# TSOC_CYBLE_R1_0.net
KiCad netlist of a schematic drawn in EAGLE
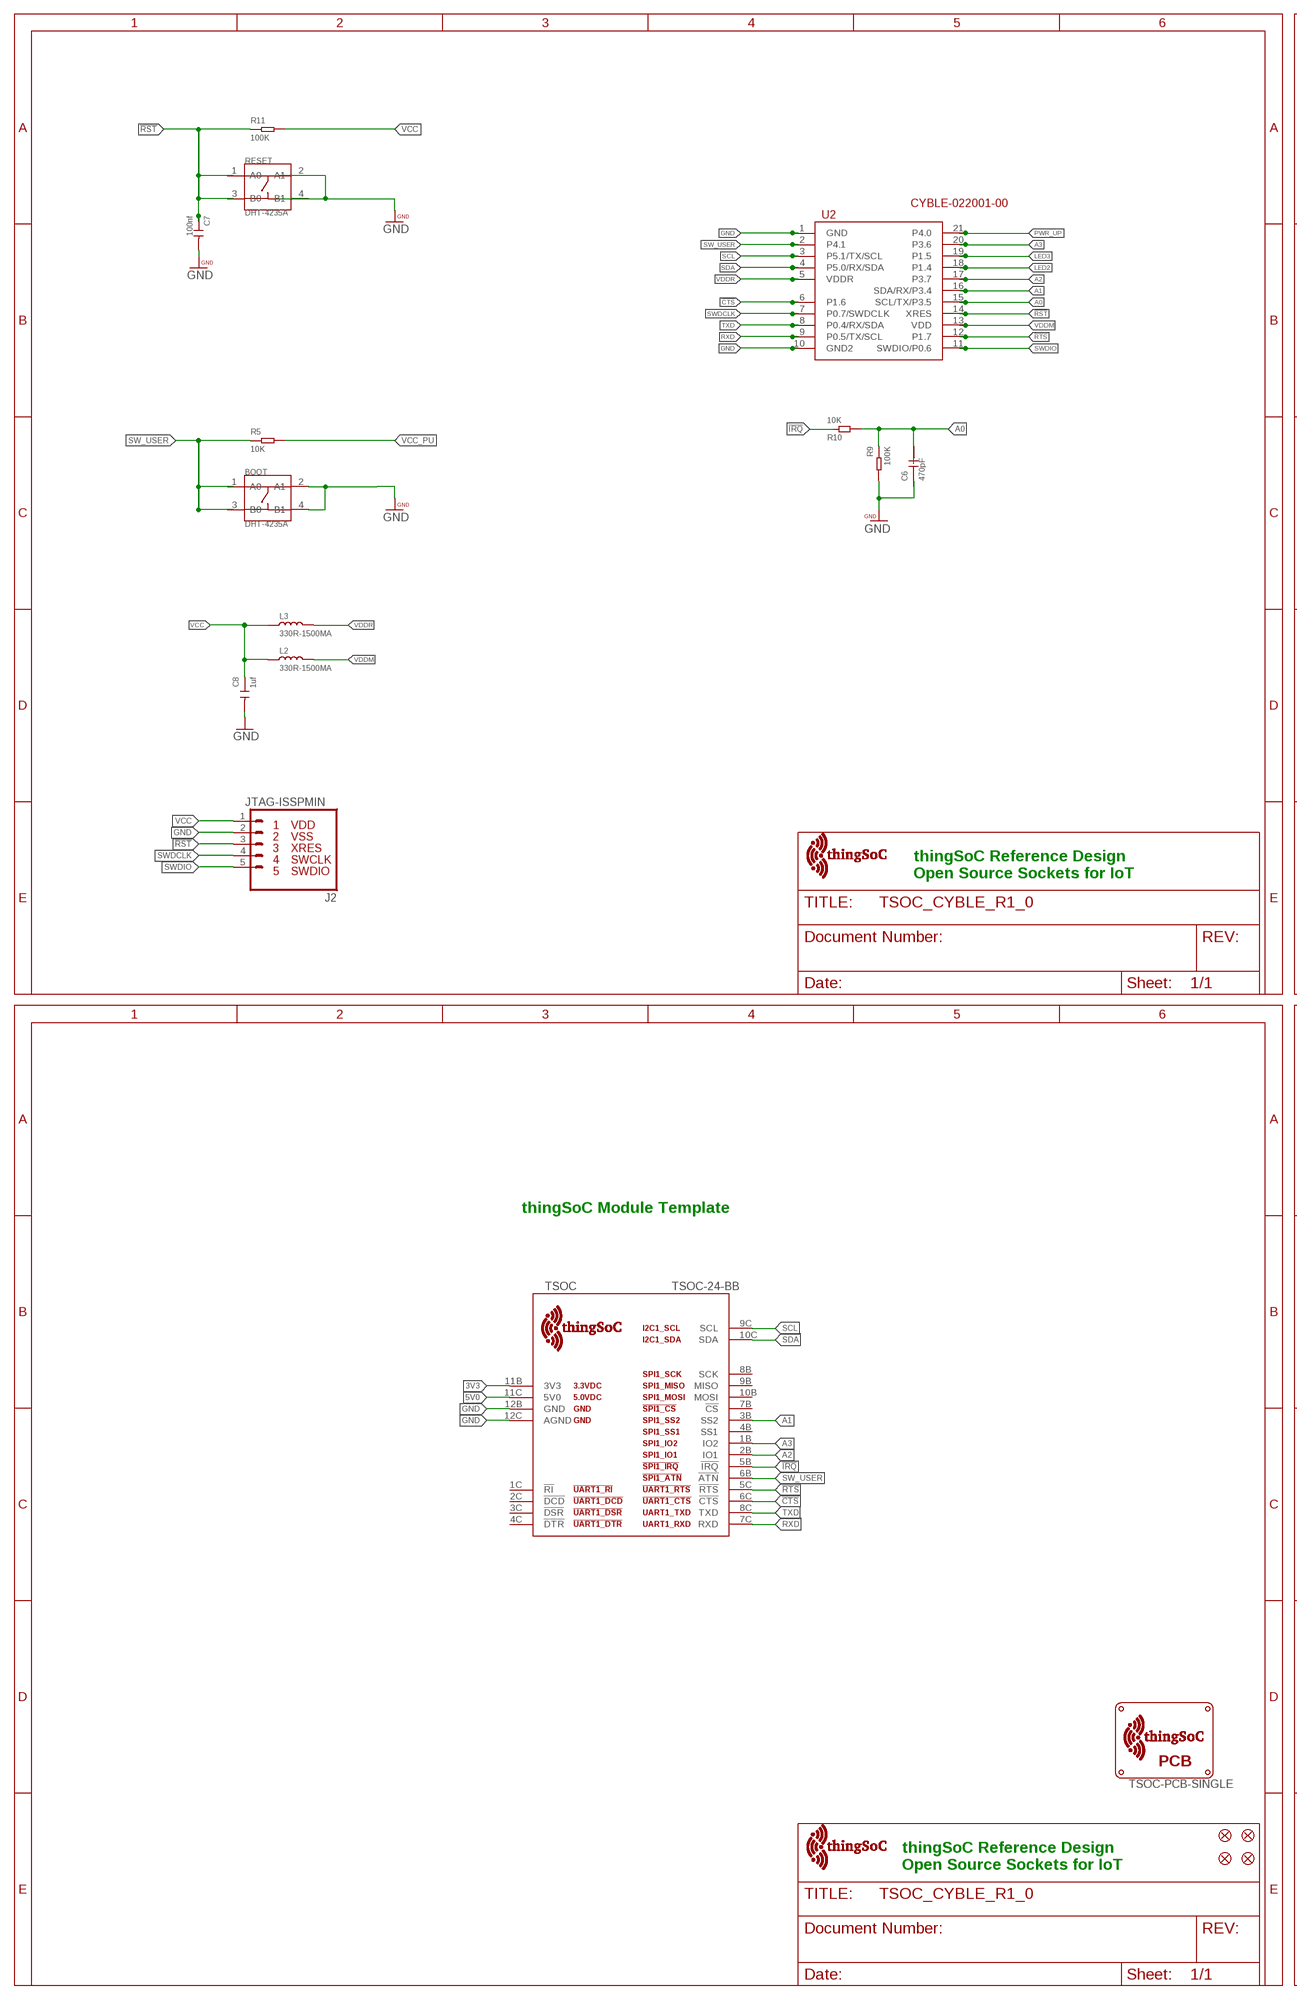
[diagram p0: schematic, sheet 1, part 1 of 2]
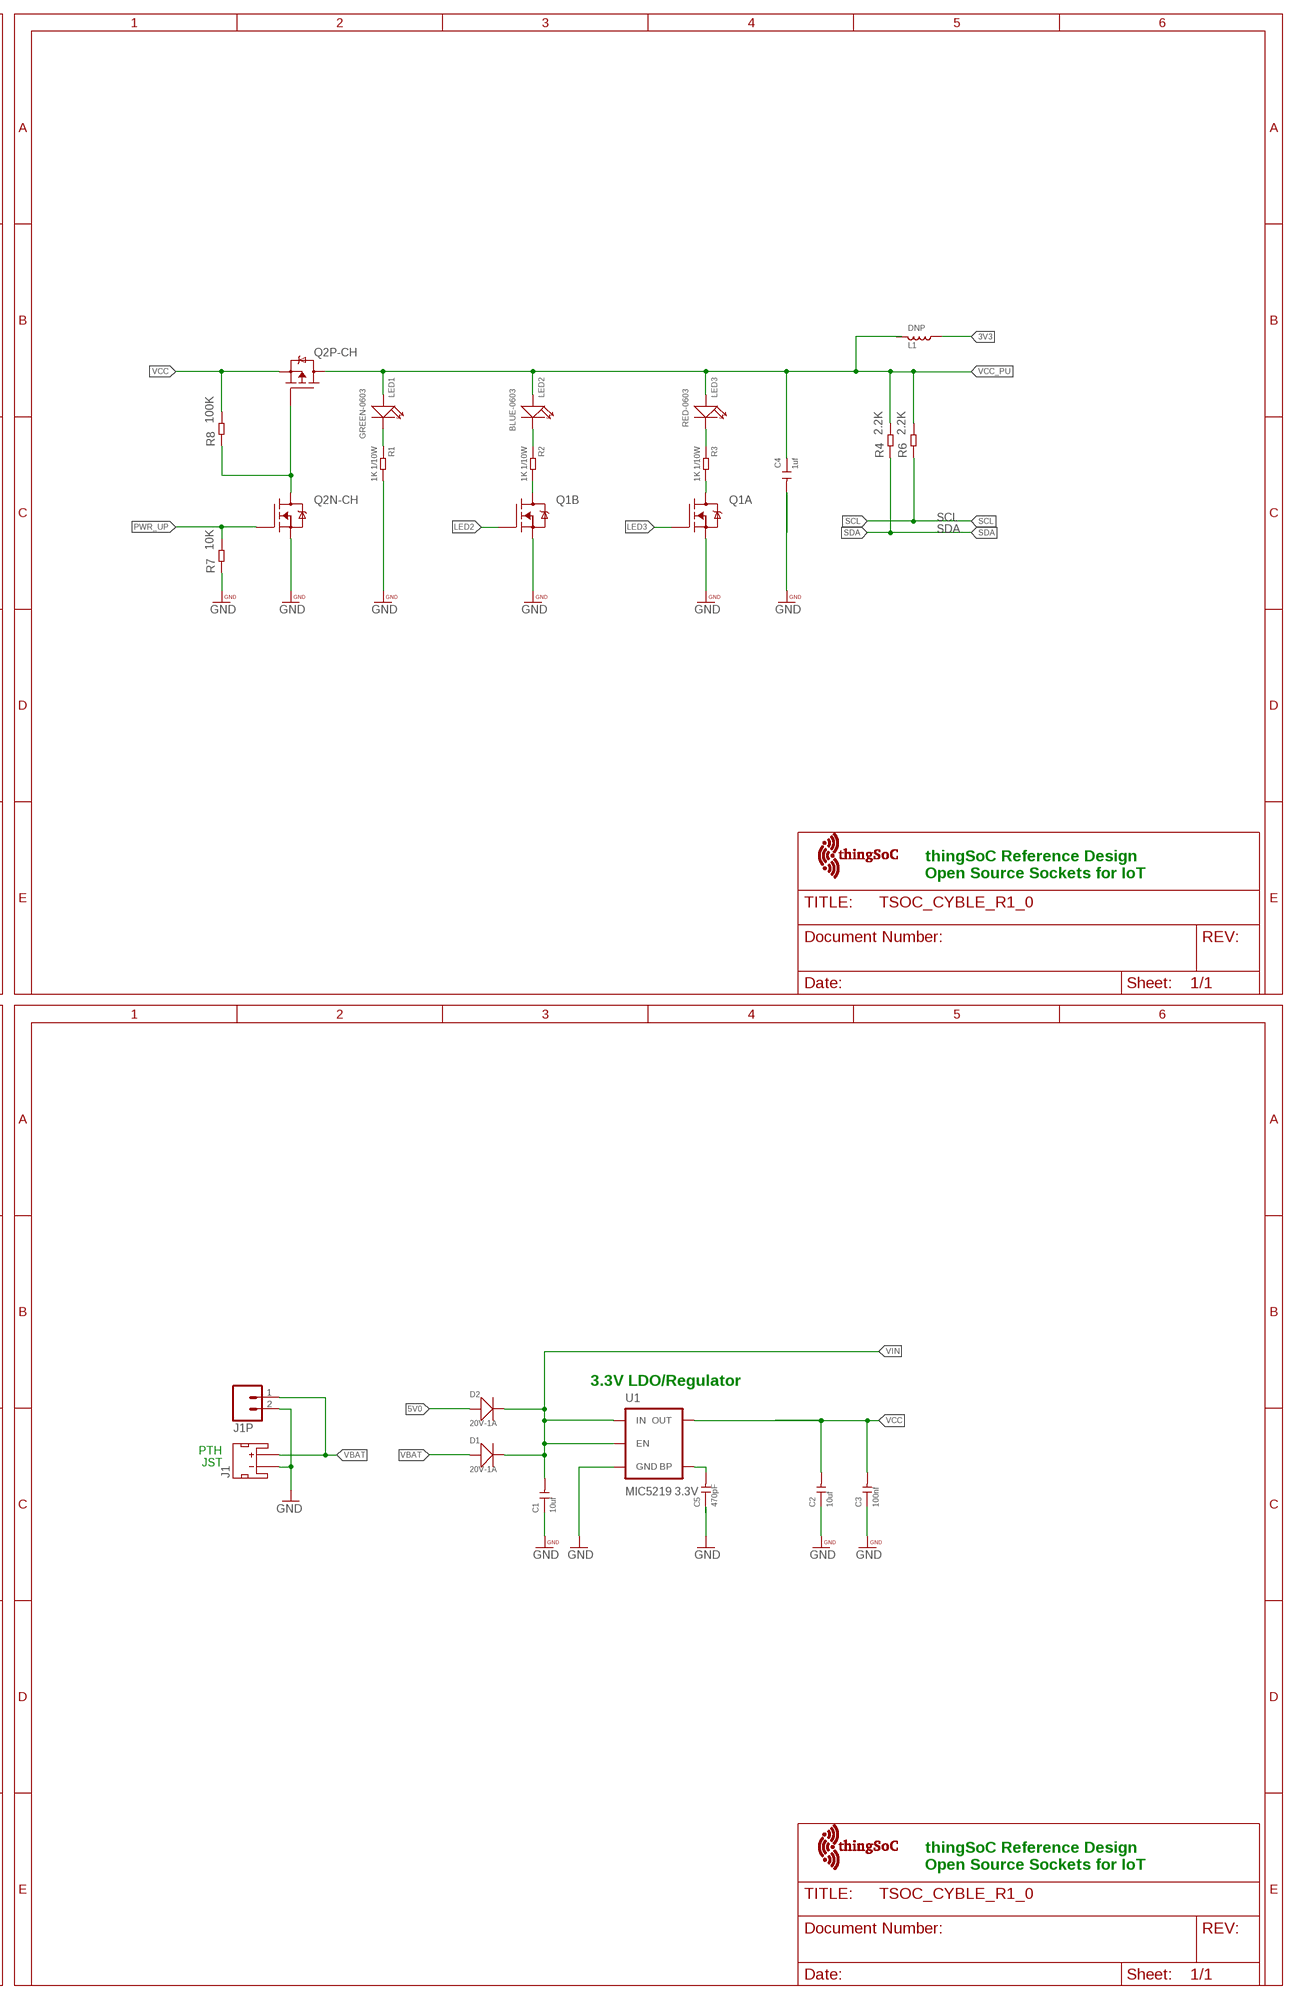
[diagram p1: schematic, sheet 1, part 2 of 2]

(export (version "E")
  (design (tool "Eeschema 10.0.6"))
  (components
    (comp (ref "$$U$1")
      (value "TSOC-LOGO-MED")
      (footprint "eagle-import:TSOC-LOGO-MED")
      (libsource (lib "eagle-import") (part "TSOC-LOGO-MED"))
    )
    (comp (ref "$$U$2")
      (value "TSOC-LOGO-MED")
      (footprint "eagle-import:TSOC-LOGO-MED")
      (libsource (lib "eagle-import") (part "TSOC-LOGO-MED"))
    )
    (comp (ref "BOOT")
      (value "DHT-4235A")
      (footprint "eagle-import:SW4-SMD-4.2X3.2X2.5MM")
      (libsource (lib "eagle-import") (part "SMD-BUTTON-TOP-DHT-4235A(4P-4.2X3.2MM)"))
    )
    (comp (ref "C1")
      (value "10uf")
      (footprint "eagle-import:C1206")
      (fields (field (name "MPN") "CC1206KKX5R8BB106"))
      (libsource (lib "eagle-import") (part "CERAMIC-10UF-25V-10%-X5R(1206)"))
    )
    (comp (ref "C2")
      (value "10uf")
      (footprint "eagle-import:C1206")
      (fields (field (name "MPN") "CC1206KKX5R8BB106"))
      (libsource (lib "eagle-import") (part "CERAMIC-10UF-25V-10%-X5R(1206)"))
    )
    (comp (ref "C3")
      (value "100nf")
      (footprint "eagle-import:C0603")
      (fields (field (name "MPN") "CC0603KRX7R9BB104"))
      (libsource (lib "eagle-import") (part "CERAMIC-100NF-50V-10%-X7R(0603)"))
    )
    (comp (ref "C4")
      (value "1uf")
      (footprint "eagle-import:C0603")
      (fields (field (name "MPN") "CC0603KRX7R8BB105"))
      (libsource (lib "eagle-import") (part "CERAMIC-1UF-25V-10%-X7R(0603)"))
    )
    (comp (ref "C5")
      (value "470pF")
      (footprint "eagle-import:C0603")
      (fields (field (name "MPN") "CC0603KRX7R9BB104"))
      (libsource (lib "eagle-import") (part "CERAMIC-100NF-50V-10%-X7R(0603)"))
    )
    (comp (ref "C6")
      (value "470pF")
      (footprint "eagle-import:C0603")
      (fields (field (name "MPN") "CC0603KRX7R9BB104"))
      (libsource (lib "eagle-import") (part "CERAMIC-100NF-50V-10%-X7R(0603)"))
    )
    (comp (ref "C7")
      (value "100nf")
      (footprint "eagle-import:C0603")
      (fields (field (name "MPN") "CC0603KRX7R9BB104"))
      (libsource (lib "eagle-import") (part "CERAMIC-100NF-50V-10%-X7R(0603)"))
    )
    (comp (ref "C8")
      (value "1uf")
      (footprint "eagle-import:C0603")
      (fields (field (name "MPN") "CC0603KRX7R8BB105"))
      (libsource (lib "eagle-import") (part "CERAMIC-1UF-25V-10%-X7R(0603)"))
    )
    (comp (ref "D1")
      (value "20V-1A")
      (footprint "eagle-import:SOD-123")
      (fields (field (name "MPN") "B5819W"))
      (libsource (lib "eagle-import") (part "SMD-DIODE-SCHOTTKY-20V-1A(SOD-123)"))
    )
    (comp (ref "D2")
      (value "20V-1A")
      (footprint "eagle-import:SOD-123")
      (fields (field (name "MPN") "B5819W"))
      (libsource (lib "eagle-import") (part "SMD-DIODE-SCHOTTKY-20V-1A(SOD-123)"))
    )
    (comp (ref "FID1")
      (value "FIDUCIALUFIDUCIAL")
      (footprint "eagle-import:MICRO-FIDUCIAL")
      (libsource (lib "eagle-import") (part "FIDUCIALUFIDUCIAL"))
    )
    (comp (ref "FID2")
      (value "FIDUCIALUFIDUCIAL")
      (footprint "eagle-import:MICRO-FIDUCIAL")
      (libsource (lib "eagle-import") (part "FIDUCIALUFIDUCIAL"))
    )
    (comp (ref "FID3")
      (value "FIDUCIALUFIDUCIAL")
      (footprint "eagle-import:MICRO-FIDUCIAL")
      (libsource (lib "eagle-import") (part "FIDUCIALUFIDUCIAL"))
    )
    (comp (ref "FID4")
      (value "FIDUCIALUFIDUCIAL")
      (footprint "eagle-import:MICRO-FIDUCIAL")
      (libsource (lib "eagle-import") (part "FIDUCIALUFIDUCIAL"))
    )
    (comp (ref "J1")
      (value "JST_2MM_MALE")
      (footprint "eagle-import:JST-2-SMD")
      (libsource (lib "eagle-import") (part "JST_2MM_MALE"))
    )
    (comp (ref "J1P")
      (value "M02-JST-2-PTH-NO_SILK")
      (footprint "eagle-import:JST-2-PTH-NS")
      (libsource (lib "eagle-import") (part "M02-JST-2-PTH-NO_SILK"))
    )
    (comp (ref "J2")
      (value "JTAG-ISSPMIN")
      (footprint "eagle-import:PSOC_JTAG_MINSILK")
      (libsource (lib "eagle-import") (part "JTAG-ISSPMIN"))
    )
    (comp (ref "L1")
      (value "DNP")
      (footprint "eagle-import:L0603")
      (fields (field (name "MPN") "BLM18AG121SN1D"))
      (libsource (lib "eagle-import") (part "SMD-FERRITE-CHIP-120-OHM-500MA(0603)"))
    )
    (comp (ref "L2")
      (value "330R-1500MA")
      (footprint "eagle-import:L0805")
      (fields (field (name "MPN") "BLM21PG331SN1D"))
      (libsource (lib "eagle-import") (part "SMD-FERRITE-BEAD-330R-1500MA(0805)'0805'"))
    )
    (comp (ref "L3")
      (value "330R-1500MA")
      (footprint "eagle-import:L0805")
      (fields (field (name "MPN") "BLM21PG331SN1D"))
      (libsource (lib "eagle-import") (part "SMD-FERRITE-BEAD-330R-1500MA(0805)'0805'"))
    )
    (comp (ref "LED1")
      (value "GREEN-0603")
      (footprint "eagle-import:LED-0603")
      (fields (field (name "MPN") "19-217-G7C-AN1P2-3T"))
      (libsource (lib "eagle-import") (part "SMD-LED-CLEAR-GREEN(0603)"))
    )
    (comp (ref "LED2")
      (value "BLUE-0603")
      (footprint "eagle-import:LED-0603")
      (fields (field (name "MPN") "19-217-G7C-AN1P2-3T"))
      (libsource (lib "eagle-import") (part "SMD-LED-CLEAR-GREEN(0603)"))
    )
    (comp (ref "LED3")
      (value "RED-0603")
      (footprint "eagle-import:LED-0603")
      (fields (field (name "MPN") "19-217-R6C-AL1M2VY-3T"))
      (libsource (lib "eagle-import") (part "LED-SMD-RED-DIFFUSED(0603)"))
    )
    (comp (ref "PCB")
      (value "TSOC-PCB-SINGLE")
      (footprint "eagle-import:TSOC-BB-BRD-DIM")
      (libsource (lib "eagle-import") (part "TSOC-PCB-SINGLE"))
    )
    (comp (ref "Q1")
      (value "FDG1024NZ")
      (footprint "eagle-import:SOT95P280X110-6N")
      (libsource (lib "eagle-import") (part "FDG1024NZ"))
    )
    (comp (ref "Q2")
      (value "FDC6420C")
      (footprint "eagle-import:SOT95P280X110-6N")
      (libsource (lib "eagle-import") (part "FDC6420C"))
    )
    (comp (ref "R1")
      (value "1K 1/10W")
      (footprint "eagle-import:R0603")
      (fields (field (name "MPN") "RC0603JR-071KL"))
      (libsource (lib "eagle-import") (part "SMD-RES-1K-5%-1/10W(0603)"))
    )
    (comp (ref "R2")
      (value "1K 1/10W")
      (footprint "eagle-import:R0603")
      (fields (field (name "MPN") "RC0603JR-071KL"))
      (libsource (lib "eagle-import") (part "SMD-RES-1K-5%-1/10W(0603)"))
    )
    (comp (ref "R3")
      (value "1K 1/10W")
      (footprint "eagle-import:R0603")
      (fields (field (name "MPN") "RC0603JR-071KL"))
      (libsource (lib "eagle-import") (part "SMD-RES-1K-5%-1/10W(0603)"))
    )
    (comp (ref "R4")
      (value "2.2K")
      (footprint "eagle-import:R0603")
      (fields (field (name "MPN") "RC0603JR-072K2L"))
      (libsource (lib "eagle-import") (part "SMD-RES-2.2K-5%-1/10W(0603)"))
    )
    (comp (ref "R5")
      (value "10K")
      (footprint "eagle-import:R0603")
      (fields (field (name "MPN") "RC0603FR-0710KL"))
      (libsource (lib "eagle-import") (part "SMD-RES-10K-1%-1/10W(0603)"))
    )
    (comp (ref "R6")
      (value "2.2K")
      (footprint "eagle-import:R0603")
      (fields (field (name "MPN") "RC0603JR-072K2L"))
      (libsource (lib "eagle-import") (part "SMD-RES-2.2K-5%-1/10W(0603)"))
    )
    (comp (ref "R7")
      (value "10K")
      (footprint "eagle-import:R0603")
      (fields (field (name "MPN") "RC0603FR-0710KL"))
      (libsource (lib "eagle-import") (part "SMD-RES-10K-1%-1/10W(0603)"))
    )
    (comp (ref "R8")
      (value "100K")
      (footprint "eagle-import:R0603")
      (fields (field (name "MPN") "RC0603FR-0710KL"))
      (libsource (lib "eagle-import") (part "SMD-RES-10K-1%-1/10W(0603)"))
    )
    (comp (ref "R9")
      (value "100K")
      (footprint "eagle-import:R0603")
      (fields (field (name "MPN") "RC0603FR-07100KL"))
      (libsource (lib "eagle-import") (part "SMD-RES-100K-1%-1/10W(0603)"))
    )
    (comp (ref "R10")
      (value "10K")
      (footprint "eagle-import:R0603")
      (fields (field (name "MPN") "RC0603FR-07100KL"))
      (libsource (lib "eagle-import") (part "SMD-RES-100K-1%-1/10W(0603)"))
    )
    (comp (ref "R11")
      (value "100K")
      (footprint "eagle-import:R0603")
      (fields (field (name "MPN") "RC0603FR-0710KL"))
      (libsource (lib "eagle-import") (part "SMD-RES-10K-1%-1/10W(0603)"))
    )
    (comp (ref "RESET")
      (value "DHT-4235A")
      (footprint "eagle-import:SW4-SMD-4.2X3.2X2.5MM")
      (libsource (lib "eagle-import") (part "SMD-BUTTON-TOP-DHT-4235A(4P-4.2X3.2MM)"))
    )
    (comp (ref "TSOC")
      (value "TSOC-24-BB")
      (footprint "eagle-import:TSOC-BB-S24")
      (libsource (lib "eagle-import") (part "TSOC-24-BB"))
    )
    (comp (ref "U$100")
      (value "TSOC-LOGO-MED")
      (footprint "eagle-import:TSOC-LOGO-MED")
      (libsource (lib "eagle-import") (part "TSOC-LOGO-MED"))
    )
    (comp (ref "U$101")
      (value "TSOC-LOGO-MED")
      (footprint "eagle-import:TSOC-LOGO-MED")
      (libsource (lib "eagle-import") (part "TSOC-LOGO-MED"))
    )
    (comp (ref "U1")
      (value "MIC5219 3.3V")
      (footprint "eagle-import:SOT23-5")
      (libsource (lib "eagle-import") (part "V_REG_MIC52193.3V"))
    )
    (comp (ref "U2")
      (value "CYBLE-022001-00")
      (footprint "eagle-import:PROC-BLE-10MM-21")
      (libsource (lib "eagle-import") (part "CYBLE-022001-00"))
    )
  )
  (nets
    (net (code "1") (name "/~{CTS}") (class "Default")
      (node (ref "TSOC") (pin "6C") (pinfunction "~{CTS}_6C") (pintype "bidirectional"))
      (node (ref "U2") (pin "6") (pinfunction "P1.6_6") (pintype "bidirectional"))
    )
    (net (code "2") (name "/~{IRQ}") (class "Default")
      (node (ref "R10") (pin "1") (pinfunction "1_1") (pintype "passive"))
      (node (ref "TSOC") (pin "5B") (pinfunction "~{IRQ}_5B") (pintype "bidirectional"))
    )
    (net (code "3") (name "/~{RST}") (class "Default")
      (node (ref "C7") (pin "1") (pinfunction "1_1") (pintype "passive"))
      (node (ref "J2") (pin "3") (pinfunction "3_3") (pintype "passive"))
      (node (ref "R11") (pin "1") (pinfunction "1_1") (pintype "passive"))
      (node (ref "RESET") (pin "1") (pinfunction "A0_1") (pintype "bidirectional"))
      (node (ref "RESET") (pin "3") (pinfunction "B0_3") (pintype "bidirectional"))
      (node (ref "U2") (pin "14") (pinfunction "XRES_14") (pintype "input"))
    )
    (net (code "4") (name "/~{RTS}") (class "Default")
      (node (ref "TSOC") (pin "5C") (pinfunction "~{RTS}_5C") (pintype "bidirectional"))
      (node (ref "U2") (pin "12") (pinfunction "P1.7_12") (pintype "bidirectional"))
    )
    (net (code "5") (name "3V3") (class "Default")
      (node (ref "L1") (pin "2") (pinfunction "2_2") (pintype "passive"))
      (node (ref "TSOC") (pin "11B") (pinfunction "3V3_11B") (pintype "bidirectional"))
    )
    (net (code "6") (name "5V0") (class "Default")
      (node (ref "D2") (pin "+") (pinfunction "+_+") (pintype "passive"))
      (node (ref "TSOC") (pin "11C") (pinfunction "5V0_11C") (pintype "bidirectional"))
    )
    (net (code "7") (name "A0") (class "Default")
      (node (ref "C6") (pin "2") (pinfunction "2_2") (pintype "passive"))
      (node (ref "R10") (pin "2") (pinfunction "2_2") (pintype "passive"))
      (node (ref "R9") (pin "1") (pinfunction "1_1") (pintype "passive"))
      (node (ref "U2") (pin "15") (pinfunction "SCL/TX/P3.5_15") (pintype "bidirectional"))
    )
    (net (code "8") (name "A1") (class "Default")
      (node (ref "TSOC") (pin "3B") (pinfunction "SS2_3B") (pintype "bidirectional"))
      (node (ref "U2") (pin "16") (pinfunction "SDA/RX/P3.4_16") (pintype "bidirectional"))
    )
    (net (code "9") (name "A2") (class "Default")
      (node (ref "TSOC") (pin "2B") (pinfunction "IO1_2B") (pintype "bidirectional"))
      (node (ref "U2") (pin "17") (pinfunction "P3.7_17") (pintype "bidirectional"))
    )
    (net (code "10") (name "A3") (class "Default")
      (node (ref "TSOC") (pin "1B") (pinfunction "IO2_1B") (pintype "bidirectional"))
      (node (ref "U2") (pin "20") (pinfunction "P3.6_20") (pintype "bidirectional"))
    )
    (net (code "11") (name "GND") (class "Default")
      (node (ref "BOOT") (pin "2") (pinfunction "A1_2") (pintype "bidirectional"))
      (node (ref "BOOT") (pin "4") (pinfunction "B1_4") (pintype "bidirectional"))
      (node (ref "C1") (pin "1") (pinfunction "1_1") (pintype "passive"))
      (node (ref "C2") (pin "1") (pinfunction "1_1") (pintype "passive"))
      (node (ref "C3") (pin "1") (pinfunction "1_1") (pintype "passive"))
      (node (ref "C4") (pin "2") (pinfunction "2_2") (pintype "passive"))
      (node (ref "C5") (pin "1") (pinfunction "1_1") (pintype "passive"))
      (node (ref "C6") (pin "1") (pinfunction "1_1") (pintype "passive"))
      (node (ref "C7") (pin "2") (pinfunction "2_2") (pintype "passive"))
      (node (ref "C8") (pin "2") (pinfunction "2_2") (pintype "passive"))
      (node (ref "J1") (pin "1") (pinfunction "-_1") (pintype "bidirectional"))
      (node (ref "J1P") (pin "2") (pinfunction "2_2") (pintype "passive"))
      (node (ref "J2") (pin "2") (pinfunction "2_2") (pintype "passive"))
      (node (ref "Q1") (pin "1") (pinfunction "S_1") (pintype "passive"))
      (node (ref "Q1") (pin "4") (pinfunction "S_4") (pintype "passive"))
      (node (ref "Q2") (pin "5") (pinfunction "S_5") (pintype "passive"))
      (node (ref "R1") (pin "2") (pinfunction "2_2") (pintype "passive"))
      (node (ref "R7") (pin "1") (pinfunction "1_1") (pintype "passive"))
      (node (ref "R9") (pin "2") (pinfunction "2_2") (pintype "passive"))
      (node (ref "RESET") (pin "2") (pinfunction "A1_2") (pintype "bidirectional"))
      (node (ref "RESET") (pin "4") (pinfunction "B1_4") (pintype "bidirectional"))
      (node (ref "TSOC") (pin "12B") (pinfunction "GND_12B") (pintype "bidirectional"))
      (node (ref "TSOC") (pin "12C") (pinfunction "AGND_12C") (pintype "bidirectional"))
      (node (ref "U1") (pin "2") (pinfunction "GND_2") (pintype "input"))
      (node (ref "U2") (pin "1") (pinfunction "GND_1") (pintype "power_in"))
      (node (ref "U2") (pin "10") (pinfunction "GND2_10") (pintype "power_in"))
    )
    (net (code "12") (name "LED2") (class "Default")
      (node (ref "Q1") (pin "5") (pinfunction "G_5") (pintype "passive"))
      (node (ref "U2") (pin "18") (pinfunction "P1.4_18") (pintype "bidirectional"))
    )
    (net (code "13") (name "LED3") (class "Default")
      (node (ref "Q1") (pin "2") (pinfunction "G_2") (pintype "passive"))
      (node (ref "U2") (pin "19") (pinfunction "P1.5_19") (pintype "bidirectional"))
    )
    (net (code "14") (name "Net-(LED1-Pad-)") (class "Default")
      (node (ref "LED1") (pin "-") (pinfunction "-_-") (pintype "passive"))
      (node (ref "R1") (pin "1") (pinfunction "1_1") (pintype "passive"))
    )
    (net (code "15") (name "Net-(LED2-Pad-)") (class "Default")
      (node (ref "LED2") (pin "-") (pinfunction "-_-") (pintype "passive"))
      (node (ref "R2") (pin "1") (pinfunction "1_1") (pintype "passive"))
    )
    (net (code "16") (name "Net-(LED3-Pad-)") (class "Default")
      (node (ref "LED3") (pin "-") (pinfunction "-_-") (pintype "passive"))
      (node (ref "R3") (pin "1") (pinfunction "1_1") (pintype "passive"))
    )
    (net (code "17") (name "Net-(Q1A-D)") (class "Default")
      (node (ref "Q1") (pin "6") (pinfunction "D_6") (pintype "passive"))
      (node (ref "R3") (pin "2") (pinfunction "2_2") (pintype "passive"))
    )
    (net (code "18") (name "Net-(Q1B-D)") (class "Default")
      (node (ref "Q1") (pin "3") (pinfunction "D_3") (pintype "passive"))
      (node (ref "R2") (pin "2") (pinfunction "2_2") (pintype "passive"))
    )
    (net (code "19") (name "Net-(Q2A-D)") (class "Default")
      (node (ref "Q2") (pin "3") (pinfunction "G_3") (pintype "passive"))
      (node (ref "Q2") (pin "6") (pinfunction "D_6") (pintype "passive"))
      (node (ref "R8") (pin "1") (pinfunction "1_1") (pintype "passive"))
    )
    (net (code "20") (name "Net-(U1-BP)") (class "Default")
      (node (ref "C5") (pin "2") (pinfunction "2_2") (pintype "passive"))
      (node (ref "U1") (pin "4") (pinfunction "BP_4") (pintype "input"))
    )
    (net (code "21") (name "PWR_UP") (class "Default")
      (node (ref "Q2") (pin "1") (pinfunction "G_1") (pintype "passive"))
      (node (ref "R7") (pin "2") (pinfunction "2_2") (pintype "passive"))
      (node (ref "U2") (pin "21") (pinfunction "P4.0_21") (pintype "bidirectional"))
    )
    (net (code "22") (name "RXD") (class "Default")
      (node (ref "TSOC") (pin "7C") (pinfunction "RXD_7C") (pintype "bidirectional"))
      (node (ref "U2") (pin "9") (pinfunction "P0.5/TX/SCL_9") (pintype "bidirectional"))
    )
    (net (code "23") (name "SCL") (class "Default")
      (node (ref "R6") (pin "1") (pinfunction "1_1") (pintype "passive"))
      (node (ref "TSOC") (pin "9C") (pinfunction "SCL_9C") (pintype "bidirectional"))
      (node (ref "U2") (pin "3") (pinfunction "P5.1/TX/SCL_3") (pintype "bidirectional"))
    )
    (net (code "24") (name "SDA") (class "Default")
      (node (ref "R4") (pin "1") (pinfunction "1_1") (pintype "passive"))
      (node (ref "TSOC") (pin "10C") (pinfunction "SDA_10C") (pintype "bidirectional"))
      (node (ref "U2") (pin "4") (pinfunction "P5.0/RX/SDA_4") (pintype "bidirectional"))
    )
    (net (code "25") (name "SWDCLK") (class "Default")
      (node (ref "J2") (pin "4") (pinfunction "4_4") (pintype "passive"))
      (node (ref "U2") (pin "7") (pinfunction "P0.7/SWDCLK_7") (pintype "bidirectional"))
    )
    (net (code "26") (name "SWDIO") (class "Default")
      (node (ref "J2") (pin "5") (pinfunction "5_5") (pintype "passive"))
      (node (ref "U2") (pin "11") (pinfunction "SWDIO/P0.6_11") (pintype "bidirectional"))
    )
    (net (code "27") (name "SW_USER") (class "Default")
      (node (ref "BOOT") (pin "1") (pinfunction "A0_1") (pintype "bidirectional"))
      (node (ref "BOOT") (pin "3") (pinfunction "B0_3") (pintype "bidirectional"))
      (node (ref "R5") (pin "1") (pinfunction "1_1") (pintype "passive"))
      (node (ref "TSOC") (pin "6B") (pinfunction "~{ATN}_6B") (pintype "bidirectional"))
      (node (ref "U2") (pin "2") (pinfunction "P4.1_2") (pintype "bidirectional"))
    )
    (net (code "28") (name "TXD") (class "Default")
      (node (ref "TSOC") (pin "8C") (pinfunction "TXD_8C") (pintype "bidirectional"))
      (node (ref "U2") (pin "8") (pinfunction "P0.4/RX/SDA_8") (pintype "bidirectional"))
    )
    (net (code "29") (name "VBAT") (class "Default")
      (node (ref "D1") (pin "+") (pinfunction "+_+") (pintype "passive"))
      (node (ref "J1") (pin "2") (pinfunction "+_2") (pintype "bidirectional"))
      (node (ref "J1P") (pin "1") (pinfunction "1_1") (pintype "passive"))
    )
    (net (code "30") (name "VCC") (class "Default")
      (node (ref "C2") (pin "2") (pinfunction "2_2") (pintype "passive"))
      (node (ref "C3") (pin "2") (pinfunction "2_2") (pintype "passive"))
      (node (ref "C8") (pin "1") (pinfunction "1_1") (pintype "passive"))
      (node (ref "J2") (pin "1") (pinfunction "1_1") (pintype "passive"))
      (node (ref "L2") (pin "1") (pinfunction "1_1") (pintype "passive"))
      (node (ref "L3") (pin "1") (pinfunction "1_1") (pintype "passive"))
      (node (ref "Q2") (pin "2") (pinfunction "S_2") (pintype "passive"))
      (node (ref "R11") (pin "2") (pinfunction "2_2") (pintype "passive"))
      (node (ref "R8") (pin "2") (pinfunction "2_2") (pintype "passive"))
      (node (ref "U1") (pin "5") (pinfunction "OUT_5") (pintype "passive"))
    )
    (net (code "31") (name "VCC_PU") (class "Default")
      (node (ref "C4") (pin "1") (pinfunction "1_1") (pintype "passive"))
      (node (ref "L1") (pin "1") (pinfunction "1_1") (pintype "passive"))
      (node (ref "LED1") (pin "+") (pinfunction "+_+") (pintype "passive"))
      (node (ref "LED2") (pin "+") (pinfunction "+_+") (pintype "passive"))
      (node (ref "LED3") (pin "+") (pinfunction "+_+") (pintype "passive"))
      (node (ref "Q2") (pin "4") (pinfunction "D_4") (pintype "passive"))
      (node (ref "R4") (pin "2") (pinfunction "2_2") (pintype "passive"))
      (node (ref "R5") (pin "2") (pinfunction "2_2") (pintype "passive"))
      (node (ref "R6") (pin "2") (pinfunction "2_2") (pintype "passive"))
    )
    (net (code "32") (name "VDDM") (class "Default")
      (node (ref "L2") (pin "2") (pinfunction "2_2") (pintype "passive"))
      (node (ref "U2") (pin "13") (pinfunction "VDD_13") (pintype "power_in"))
    )
    (net (code "33") (name "VDDR") (class "Default")
      (node (ref "L3") (pin "2") (pinfunction "2_2") (pintype "passive"))
      (node (ref "U2") (pin "5") (pinfunction "VDDR_5") (pintype "power_in"))
    )
    (net (code "34") (name "VIN") (class "Default")
      (node (ref "C1") (pin "2") (pinfunction "2_2") (pintype "passive"))
      (node (ref "D1") (pin "-") (pinfunction "-_-") (pintype "passive"))
      (node (ref "D2") (pin "-") (pinfunction "-_-") (pintype "passive"))
      (node (ref "U1") (pin "1") (pinfunction "IN_1") (pintype "input"))
      (node (ref "U1") (pin "3") (pinfunction "EN_3") (pintype "input"))
    )
    (net (code "35") (name "unconnected-(J1-PAD1-PadNC1)") (class "Default")
      (node (ref "J1") (pin "NC1") (pinfunction "PAD1_NC1") (pintype "bidirectional"))
    )
    (net (code "36") (name "unconnected-(J1-PAD2-PadNC2)") (class "Default")
      (node (ref "J1") (pin "NC2") (pinfunction "PAD2_NC2") (pintype "bidirectional"))
    )
    (net (code "37") (name "unconnected-(TSOC-MISO-Pad9B)") (class "Default")
      (node (ref "TSOC") (pin "9B") (pinfunction "MISO_9B") (pintype "bidirectional"))
    )
    (net (code "38") (name "unconnected-(TSOC-MOSI-Pad10B)") (class "Default")
      (node (ref "TSOC") (pin "10B") (pinfunction "MOSI_10B") (pintype "bidirectional"))
    )
    (net (code "39") (name "unconnected-(TSOC-SCK-Pad8B)") (class "Default")
      (node (ref "TSOC") (pin "8B") (pinfunction "SCK_8B") (pintype "bidirectional"))
    )
    (net (code "40") (name "unconnected-(TSOC-SS1-Pad4B)") (class "Default")
      (node (ref "TSOC") (pin "4B") (pinfunction "SS1_4B") (pintype "bidirectional"))
    )
    (net (code "41") (name "unconnected-(TSOC-~{CS}-Pad7B)") (class "Default")
      (node (ref "TSOC") (pin "7B") (pinfunction "~{CS}_7B") (pintype "bidirectional"))
    )
    (net (code "42") (name "unconnected-(TSOC-~{DCD}-Pad2C)") (class "Default")
      (node (ref "TSOC") (pin "2C") (pinfunction "~{DCD}_2C") (pintype "bidirectional"))
    )
    (net (code "43") (name "unconnected-(TSOC-~{DSR}-Pad3C)") (class "Default")
      (node (ref "TSOC") (pin "3C") (pinfunction "~{DSR}_3C") (pintype "bidirectional"))
    )
    (net (code "44") (name "unconnected-(TSOC-~{DTR}-Pad4C)") (class "Default")
      (node (ref "TSOC") (pin "4C") (pinfunction "~{DTR}_4C") (pintype "bidirectional"))
    )
    (net (code "45") (name "unconnected-(TSOC-~{RI}-Pad1C)") (class "Default")
      (node (ref "TSOC") (pin "1C") (pinfunction "~{RI}_1C") (pintype "bidirectional"))
    )
  )
)
